# potboard.net
KiCad netlist of a schematic drawn in EAGLE
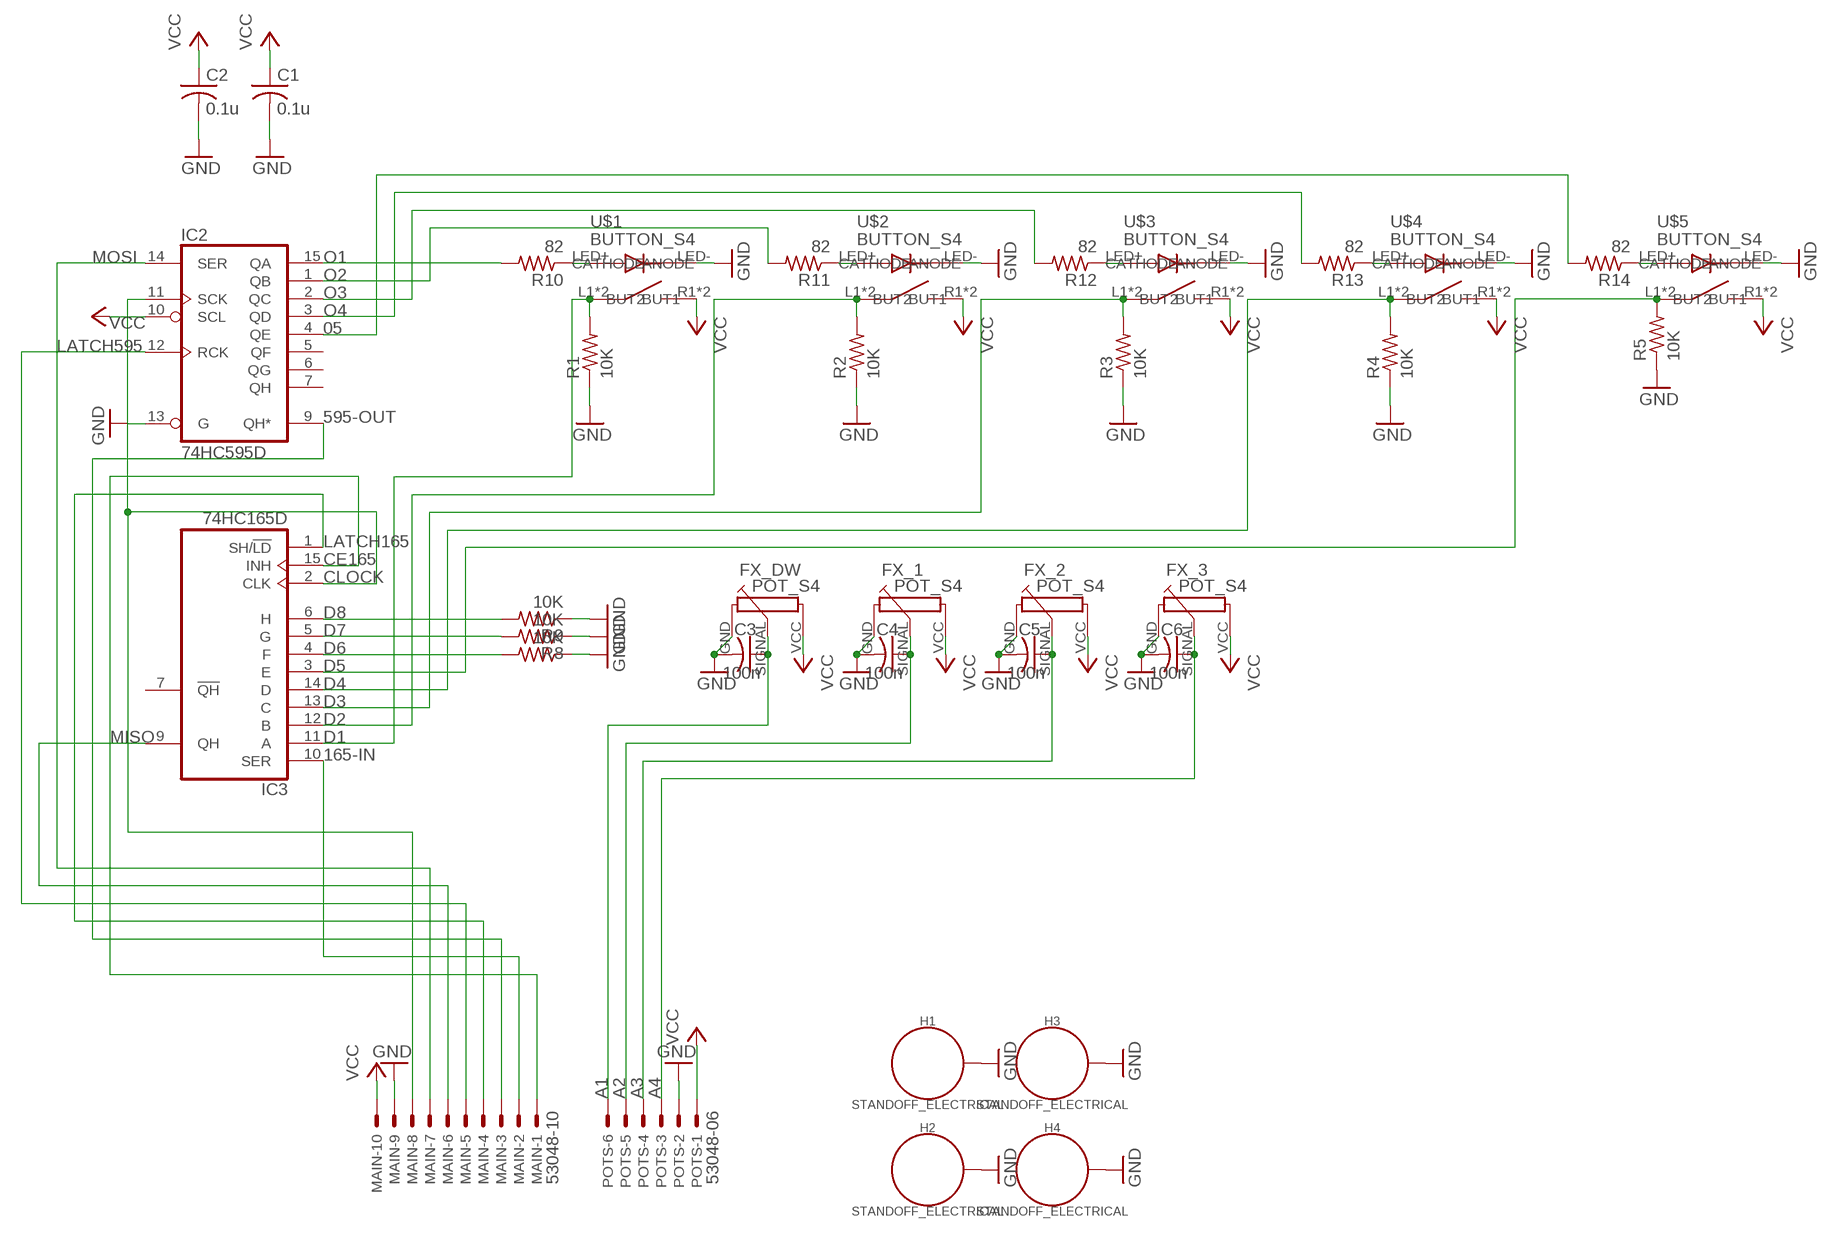
[diagram p0: schematic, sheet 1]

(export (version "E")
  (design (tool "Eeschema 10.0.6"))
  (components
    (comp (ref "C1")
      (value "0.1u")
      (footprint "eagle-import:C1206")
      (libsource (lib "eagle-import") (part "C-USC1206"))
    )
    (comp (ref "C2")
      (value "0.1u")
      (footprint "eagle-import:C1206")
      (libsource (lib "eagle-import") (part "C-USC1206"))
    )
    (comp (ref "C3")
      (value "100n")
      (footprint "eagle-import:C1206")
      (libsource (lib "eagle-import") (part "C-USC1206"))
    )
    (comp (ref "C4")
      (value "100n")
      (footprint "eagle-import:C1206")
      (libsource (lib "eagle-import") (part "C-USC1206"))
    )
    (comp (ref "C5")
      (value "100n")
      (footprint "eagle-import:C1206")
      (libsource (lib "eagle-import") (part "C-USC1206"))
    )
    (comp (ref "C6")
      (value "100n")
      (footprint "eagle-import:C1206")
      (libsource (lib "eagle-import") (part "C-USC1206"))
    )
    (comp (ref "FX_1")
      (value "POT_S4")
      (footprint "eagle-import:POT_S4")
      (libsource (lib "eagle-import") (part "POT_S4"))
    )
    (comp (ref "FX_2")
      (value "POT_S4")
      (footprint "eagle-import:POT_S4")
      (libsource (lib "eagle-import") (part "POT_S4"))
    )
    (comp (ref "FX_3")
      (value "POT_S4")
      (footprint "eagle-import:POT_S4")
      (libsource (lib "eagle-import") (part "POT_S4"))
    )
    (comp (ref "FX_DW")
      (value "POT_S4")
      (footprint "eagle-import:POT_S4")
      (libsource (lib "eagle-import") (part "POT_S4"))
    )
    (comp (ref "H1")
      (value "STANDOFF_ELECTRICAL")
      (footprint "eagle-import:STANDOFF-ELECTRICAL")
      (libsource (lib "eagle-import") (part "STANDOFF_ELECTRICAL"))
    )
    (comp (ref "H2")
      (value "STANDOFF_ELECTRICAL")
      (footprint "eagle-import:STANDOFF-ELECTRICAL")
      (libsource (lib "eagle-import") (part "STANDOFF_ELECTRICAL"))
    )
    (comp (ref "H3")
      (value "STANDOFF_ELECTRICAL")
      (footprint "eagle-import:STANDOFF-ELECTRICAL")
      (libsource (lib "eagle-import") (part "STANDOFF_ELECTRICAL"))
    )
    (comp (ref "H4")
      (value "STANDOFF_ELECTRICAL")
      (footprint "eagle-import:STANDOFF-ELECTRICAL")
      (libsource (lib "eagle-import") (part "STANDOFF_ELECTRICAL"))
    )
    (comp (ref "IC2")
      (value "74HC595D")
      (footprint "eagle-import:SO16")
      (libsource (lib "eagle-import") (part "74595DHC"))
    )
    (comp (ref "IC3")
      (value "74HC165D")
      (footprint "eagle-import:SO16")
      (libsource (lib "eagle-import") (part "74165DHC"))
    )
    (comp (ref "MAIN")
      (value "53048-10")
      (footprint "eagle-import:53048-10")
      (fields (field (name "MF") "MOLEX") (field (name "MPN") "53048-1010"))
      (libsource (lib "eagle-import") (part "53?-10048"))
    )
    (comp (ref "POTS")
      (value "53048-06")
      (footprint "eagle-import:53048-06")
      (fields (field (name "MF") "WALDOM/MOLEX") (field (name "MPN") "53048-0610"))
      (libsource (lib "eagle-import") (part "53?-06048"))
    )
    (comp (ref "R1")
      (value "10K")
      (footprint "eagle-import:R0805")
      (libsource (lib "eagle-import") (part "R-US_R0805"))
    )
    (comp (ref "R2")
      (value "10K")
      (footprint "eagle-import:R0805")
      (libsource (lib "eagle-import") (part "R-US_R0805"))
    )
    (comp (ref "R3")
      (value "10K")
      (footprint "eagle-import:R0805")
      (libsource (lib "eagle-import") (part "R-US_R0805"))
    )
    (comp (ref "R4")
      (value "10K")
      (footprint "eagle-import:R0805")
      (libsource (lib "eagle-import") (part "R-US_R0805"))
    )
    (comp (ref "R5")
      (value "10K")
      (footprint "eagle-import:R0805")
      (libsource (lib "eagle-import") (part "R-US_R0805"))
    )
    (comp (ref "R6")
      (value "10K")
      (footprint "eagle-import:R0805")
      (libsource (lib "eagle-import") (part "R-US_R0805"))
    )
    (comp (ref "R8")
      (value "10K")
      (footprint "eagle-import:R0805")
      (libsource (lib "eagle-import") (part "R-US_R0805"))
    )
    (comp (ref "R9")
      (value "10K")
      (footprint "eagle-import:R0805")
      (libsource (lib "eagle-import") (part "R-US_R0805"))
    )
    (comp (ref "R10")
      (value "82")
      (footprint "eagle-import:R0805")
      (libsource (lib "eagle-import") (part "R-US_R0805"))
    )
    (comp (ref "R11")
      (value "82")
      (footprint "eagle-import:R0805")
      (libsource (lib "eagle-import") (part "R-US_R0805"))
    )
    (comp (ref "R12")
      (value "82")
      (footprint "eagle-import:R0805")
      (libsource (lib "eagle-import") (part "R-US_R0805"))
    )
    (comp (ref "R13")
      (value "82")
      (footprint "eagle-import:R0805")
      (libsource (lib "eagle-import") (part "R-US_R0805"))
    )
    (comp (ref "R14")
      (value "82")
      (footprint "eagle-import:R0805")
      (libsource (lib "eagle-import") (part "R-US_R0805"))
    )
    (comp (ref "U$1")
      (value "BUTTON_S4")
      (footprint "eagle-import:BUTTON_S4")
      (libsource (lib "eagle-import") (part "BUTTON_S4"))
    )
    (comp (ref "U$2")
      (value "BUTTON_S4")
      (footprint "eagle-import:BUTTON_S4")
      (libsource (lib "eagle-import") (part "BUTTON_S4"))
    )
    (comp (ref "U$3")
      (value "BUTTON_S4")
      (footprint "eagle-import:BUTTON_S4")
      (libsource (lib "eagle-import") (part "BUTTON_S4"))
    )
    (comp (ref "U$4")
      (value "BUTTON_S4")
      (footprint "eagle-import:BUTTON_S4")
      (libsource (lib "eagle-import") (part "BUTTON_S4"))
    )
    (comp (ref "U$5")
      (value "BUTTON_S4")
      (footprint "eagle-import:BUTTON_S4")
      (libsource (lib "eagle-import") (part "BUTTON_S4"))
    )
  )
  (nets
    (net (code "1") (name "/05") (class "Default")
      (node (ref "IC2") (pin "4") (pinfunction "QE_4") (pintype "tri_state"))
      (node (ref "R14") (pin "2") (pinfunction "2_2") (pintype "passive"))
    )
    (net (code "2") (name "/165-IN") (class "Default")
      (node (ref "IC3") (pin "10") (pinfunction "SER_10") (pintype "input"))
      (node (ref "MAIN") (pin "2") (pinfunction "S_2") (pintype "passive"))
    )
    (net (code "3") (name "/595-OUT") (class "Default")
      (node (ref "IC2") (pin "9") (pinfunction "QH*_9") (pintype "tri_state"))
      (node (ref "MAIN") (pin "3") (pinfunction "S_3") (pintype "passive"))
    )
    (net (code "4") (name "/A1") (class "Default")
      (node (ref "C3") (pin "1") (pinfunction "1_1") (pintype "passive"))
      (node (ref "FX_DW") (pin "SIGNAL") (pinfunction "1S_SIGNAL") (pintype "passive"))
      (node (ref "POTS") (pin "6") (pinfunction "S_6") (pintype "passive"))
    )
    (net (code "5") (name "/A2") (class "Default")
      (node (ref "C4") (pin "1") (pinfunction "1_1") (pintype "passive"))
      (node (ref "FX_1") (pin "SIGNAL") (pinfunction "1S_SIGNAL") (pintype "passive"))
      (node (ref "POTS") (pin "5") (pinfunction "S_5") (pintype "passive"))
    )
    (net (code "6") (name "/A3") (class "Default")
      (node (ref "C5") (pin "1") (pinfunction "1_1") (pintype "passive"))
      (node (ref "FX_2") (pin "SIGNAL") (pinfunction "1S_SIGNAL") (pintype "passive"))
      (node (ref "POTS") (pin "4") (pinfunction "S_4") (pintype "passive"))
    )
    (net (code "7") (name "/A4") (class "Default")
      (node (ref "C6") (pin "1") (pinfunction "1_1") (pintype "passive"))
      (node (ref "FX_3") (pin "SIGNAL") (pinfunction "1S_SIGNAL") (pintype "passive"))
      (node (ref "POTS") (pin "3") (pinfunction "S_3") (pintype "passive"))
    )
    (net (code "8") (name "/CE165") (class "Default")
      (node (ref "IC3") (pin "15") (pinfunction "INH_15") (pintype "input"))
      (node (ref "MAIN") (pin "1") (pinfunction "S_1") (pintype "passive"))
    )
    (net (code "9") (name "/CLOCK") (class "Default")
      (node (ref "IC2") (pin "11") (pinfunction "SCK_11") (pintype "input"))
      (node (ref "IC3") (pin "2") (pinfunction "CLK_2") (pintype "input"))
      (node (ref "MAIN") (pin "8") (pinfunction "S_8") (pintype "passive"))
    )
    (net (code "10") (name "/D1") (class "Default")
      (node (ref "IC3") (pin "11") (pinfunction "A_11") (pintype "input"))
      (node (ref "R1") (pin "2") (pinfunction "2_2") (pintype "passive"))
      (node (ref "U$1") (pin "L1") (pinfunction "BUT1_L1") (pintype "bidirectional"))
      (node (ref "U$1") (pin "L2") (pinfunction "BUT1_L2") (pintype "bidirectional"))
    )
    (net (code "11") (name "/D2") (class "Default")
      (node (ref "IC3") (pin "12") (pinfunction "B_12") (pintype "input"))
      (node (ref "R2") (pin "2") (pinfunction "2_2") (pintype "passive"))
      (node (ref "U$2") (pin "L1") (pinfunction "BUT1_L1") (pintype "bidirectional"))
      (node (ref "U$2") (pin "L2") (pinfunction "BUT1_L2") (pintype "bidirectional"))
    )
    (net (code "12") (name "/D3") (class "Default")
      (node (ref "IC3") (pin "13") (pinfunction "C_13") (pintype "input"))
      (node (ref "R3") (pin "2") (pinfunction "2_2") (pintype "passive"))
      (node (ref "U$3") (pin "L1") (pinfunction "BUT1_L1") (pintype "bidirectional"))
      (node (ref "U$3") (pin "L2") (pinfunction "BUT1_L2") (pintype "bidirectional"))
    )
    (net (code "13") (name "/D4") (class "Default")
      (node (ref "IC3") (pin "14") (pinfunction "D_14") (pintype "input"))
      (node (ref "R4") (pin "2") (pinfunction "2_2") (pintype "passive"))
      (node (ref "U$4") (pin "L1") (pinfunction "BUT1_L1") (pintype "bidirectional"))
      (node (ref "U$4") (pin "L2") (pinfunction "BUT1_L2") (pintype "bidirectional"))
    )
    (net (code "14") (name "/D5") (class "Default")
      (node (ref "IC3") (pin "3") (pinfunction "E_3") (pintype "input"))
      (node (ref "R5") (pin "2") (pinfunction "2_2") (pintype "passive"))
      (node (ref "U$5") (pin "L1") (pinfunction "BUT1_L1") (pintype "bidirectional"))
      (node (ref "U$5") (pin "L2") (pinfunction "BUT1_L2") (pintype "bidirectional"))
    )
    (net (code "15") (name "/D6") (class "Default")
      (node (ref "IC3") (pin "4") (pinfunction "F_4") (pintype "input"))
      (node (ref "R6") (pin "2") (pinfunction "2_2") (pintype "passive"))
    )
    (net (code "16") (name "/D7") (class "Default")
      (node (ref "IC3") (pin "5") (pinfunction "G_5") (pintype "input"))
      (node (ref "R8") (pin "2") (pinfunction "2_2") (pintype "passive"))
    )
    (net (code "17") (name "/D8") (class "Default")
      (node (ref "IC3") (pin "6") (pinfunction "H_6") (pintype "input"))
      (node (ref "R9") (pin "2") (pinfunction "2_2") (pintype "passive"))
    )
    (net (code "18") (name "/LATCH165") (class "Default")
      (node (ref "IC3") (pin "1") (pinfunction "SH/~{LD}_1") (pintype "input"))
      (node (ref "MAIN") (pin "4") (pinfunction "S_4") (pintype "passive"))
    )
    (net (code "19") (name "/LATCH595") (class "Default")
      (node (ref "IC2") (pin "12") (pinfunction "RCK_12") (pintype "input"))
      (node (ref "MAIN") (pin "5") (pinfunction "S_5") (pintype "passive"))
    )
    (net (code "20") (name "/MISO") (class "Default")
      (node (ref "IC3") (pin "9") (pinfunction "QH_9") (pintype "output"))
      (node (ref "MAIN") (pin "6") (pinfunction "S_6") (pintype "passive"))
    )
    (net (code "21") (name "/MOSI") (class "Default")
      (node (ref "IC2") (pin "14") (pinfunction "SER_14") (pintype "input"))
      (node (ref "MAIN") (pin "7") (pinfunction "S_7") (pintype "passive"))
    )
    (net (code "22") (name "/O1") (class "Default")
      (node (ref "IC2") (pin "15") (pinfunction "QA_15") (pintype "tri_state"))
      (node (ref "R10") (pin "2") (pinfunction "2_2") (pintype "passive"))
    )
    (net (code "23") (name "/O2") (class "Default")
      (node (ref "IC2") (pin "1") (pinfunction "QB_1") (pintype "tri_state"))
      (node (ref "R11") (pin "2") (pinfunction "2_2") (pintype "passive"))
    )
    (net (code "24") (name "/O3") (class "Default")
      (node (ref "IC2") (pin "2") (pinfunction "QC_2") (pintype "tri_state"))
      (node (ref "R12") (pin "2") (pinfunction "2_2") (pintype "passive"))
    )
    (net (code "25") (name "/O4") (class "Default")
      (node (ref "IC2") (pin "3") (pinfunction "QD_3") (pintype "tri_state"))
      (node (ref "R13") (pin "2") (pinfunction "2_2") (pintype "passive"))
    )
    (net (code "26") (name "GND") (class "Default")
      (node (ref "C1") (pin "2") (pinfunction "2_2") (pintype "passive"))
      (node (ref "C2") (pin "2") (pinfunction "2_2") (pintype "passive"))
      (node (ref "C3") (pin "2") (pinfunction "2_2") (pintype "passive"))
      (node (ref "C4") (pin "2") (pinfunction "2_2") (pintype "passive"))
      (node (ref "C5") (pin "2") (pinfunction "2_2") (pintype "passive"))
      (node (ref "C6") (pin "2") (pinfunction "2_2") (pintype "passive"))
      (node (ref "FX_1") (pin "GND") (pinfunction "1A_GND") (pintype "passive"))
      (node (ref "FX_2") (pin "GND") (pinfunction "1A_GND") (pintype "passive"))
      (node (ref "FX_3") (pin "GND") (pinfunction "1A_GND") (pintype "passive"))
      (node (ref "FX_DW") (pin "GND") (pinfunction "1A_GND") (pintype "passive"))
      (node (ref "H1") (pin "P1") (pinfunction "P$1_P1") (pintype "bidirectional"))
      (node (ref "H2") (pin "P1") (pinfunction "P$1_P1") (pintype "bidirectional"))
      (node (ref "H3") (pin "P1") (pinfunction "P$1_P1") (pintype "bidirectional"))
      (node (ref "H4") (pin "P1") (pinfunction "P$1_P1") (pintype "bidirectional"))
      (node (ref "IC2") (pin "13") (pinfunction "G_13") (pintype "input"))
      (node (ref "MAIN") (pin "9") (pinfunction "S_9") (pintype "passive"))
      (node (ref "POTS") (pin "2") (pinfunction "S_2") (pintype "passive"))
      (node (ref "R1") (pin "1") (pinfunction "1_1") (pintype "passive"))
      (node (ref "R2") (pin "1") (pinfunction "1_1") (pintype "passive"))
      (node (ref "R3") (pin "1") (pinfunction "1_1") (pintype "passive"))
      (node (ref "R4") (pin "1") (pinfunction "1_1") (pintype "passive"))
      (node (ref "R5") (pin "1") (pinfunction "1_1") (pintype "passive"))
      (node (ref "R6") (pin "1") (pinfunction "1_1") (pintype "passive"))
      (node (ref "R8") (pin "1") (pinfunction "1_1") (pintype "passive"))
      (node (ref "R9") (pin "1") (pinfunction "1_1") (pintype "passive"))
      (node (ref "U$1") (pin "LED-") (pinfunction "CATHODE_LED-") (pintype "bidirectional"))
      (node (ref "U$2") (pin "LED-") (pinfunction "CATHODE_LED-") (pintype "bidirectional"))
      (node (ref "U$3") (pin "LED-") (pinfunction "CATHODE_LED-") (pintype "bidirectional"))
      (node (ref "U$4") (pin "LED-") (pinfunction "CATHODE_LED-") (pintype "bidirectional"))
      (node (ref "U$5") (pin "LED-") (pinfunction "CATHODE_LED-") (pintype "bidirectional"))
    )
    (net (code "27") (name "Net-(U$1-ANODE)") (class "Default")
      (node (ref "R10") (pin "1") (pinfunction "1_1") (pintype "passive"))
      (node (ref "U$1") (pin "LED+") (pinfunction "ANODE_LED+") (pintype "bidirectional"))
    )
    (net (code "28") (name "Net-(U$2-ANODE)") (class "Default")
      (node (ref "R11") (pin "1") (pinfunction "1_1") (pintype "passive"))
      (node (ref "U$2") (pin "LED+") (pinfunction "ANODE_LED+") (pintype "bidirectional"))
    )
    (net (code "29") (name "Net-(U$3-ANODE)") (class "Default")
      (node (ref "R12") (pin "1") (pinfunction "1_1") (pintype "passive"))
      (node (ref "U$3") (pin "LED+") (pinfunction "ANODE_LED+") (pintype "bidirectional"))
    )
    (net (code "30") (name "Net-(U$4-ANODE)") (class "Default")
      (node (ref "R13") (pin "1") (pinfunction "1_1") (pintype "passive"))
      (node (ref "U$4") (pin "LED+") (pinfunction "ANODE_LED+") (pintype "bidirectional"))
    )
    (net (code "31") (name "Net-(U$5-ANODE)") (class "Default")
      (node (ref "R14") (pin "1") (pinfunction "1_1") (pintype "passive"))
      (node (ref "U$5") (pin "LED+") (pinfunction "ANODE_LED+") (pintype "bidirectional"))
    )
    (net (code "32") (name "VCC") (class "Default")
      (node (ref "C1") (pin "1") (pinfunction "1_1") (pintype "passive"))
      (node (ref "C2") (pin "1") (pinfunction "1_1") (pintype "passive"))
      (node (ref "FX_1") (pin "VCC") (pinfunction "1E_VCC") (pintype "passive"))
      (node (ref "FX_2") (pin "VCC") (pinfunction "1E_VCC") (pintype "passive"))
      (node (ref "FX_3") (pin "VCC") (pinfunction "1E_VCC") (pintype "passive"))
      (node (ref "FX_DW") (pin "VCC") (pinfunction "1E_VCC") (pintype "passive"))
      (node (ref "IC2") (pin "10") (pinfunction "SCL_10") (pintype "input"))
      (node (ref "MAIN") (pin "10") (pinfunction "S_10") (pintype "passive"))
      (node (ref "POTS") (pin "1") (pinfunction "S_1") (pintype "passive"))
      (node (ref "U$1") (pin "R1") (pinfunction "BUT2_R1") (pintype "bidirectional"))
      (node (ref "U$1") (pin "R2") (pinfunction "BUT2_R2") (pintype "bidirectional"))
      (node (ref "U$2") (pin "R1") (pinfunction "BUT2_R1") (pintype "bidirectional"))
      (node (ref "U$2") (pin "R2") (pinfunction "BUT2_R2") (pintype "bidirectional"))
      (node (ref "U$3") (pin "R1") (pinfunction "BUT2_R1") (pintype "bidirectional"))
      (node (ref "U$3") (pin "R2") (pinfunction "BUT2_R2") (pintype "bidirectional"))
      (node (ref "U$4") (pin "R1") (pinfunction "BUT2_R1") (pintype "bidirectional"))
      (node (ref "U$4") (pin "R2") (pinfunction "BUT2_R2") (pintype "bidirectional"))
      (node (ref "U$5") (pin "R1") (pinfunction "BUT2_R1") (pintype "bidirectional"))
      (node (ref "U$5") (pin "R2") (pinfunction "BUT2_R2") (pintype "bidirectional"))
    )
    (net (code "33") (name "unconnected-(IC2A-QF-Pad5)") (class "Default")
      (node (ref "IC2") (pin "5") (pinfunction "QF_5") (pintype "tri_state"))
    )
    (net (code "34") (name "unconnected-(IC2A-QG-Pad6)") (class "Default")
      (node (ref "IC2") (pin "6") (pinfunction "QG_6") (pintype "tri_state"))
    )
    (net (code "35") (name "unconnected-(IC2A-QH-Pad7)") (class "Default")
      (node (ref "IC2") (pin "7") (pinfunction "QH_7") (pintype "tri_state"))
    )
    (net (code "36") (name "unconnected-(IC3A-~{QH}-Pad7)") (class "Default")
      (node (ref "IC3") (pin "7") (pinfunction "~{QH}_7") (pintype "output"))
    )
  )
)
